# atx4vc.net
KiCad netlist of a schematic drawn in EAGLE
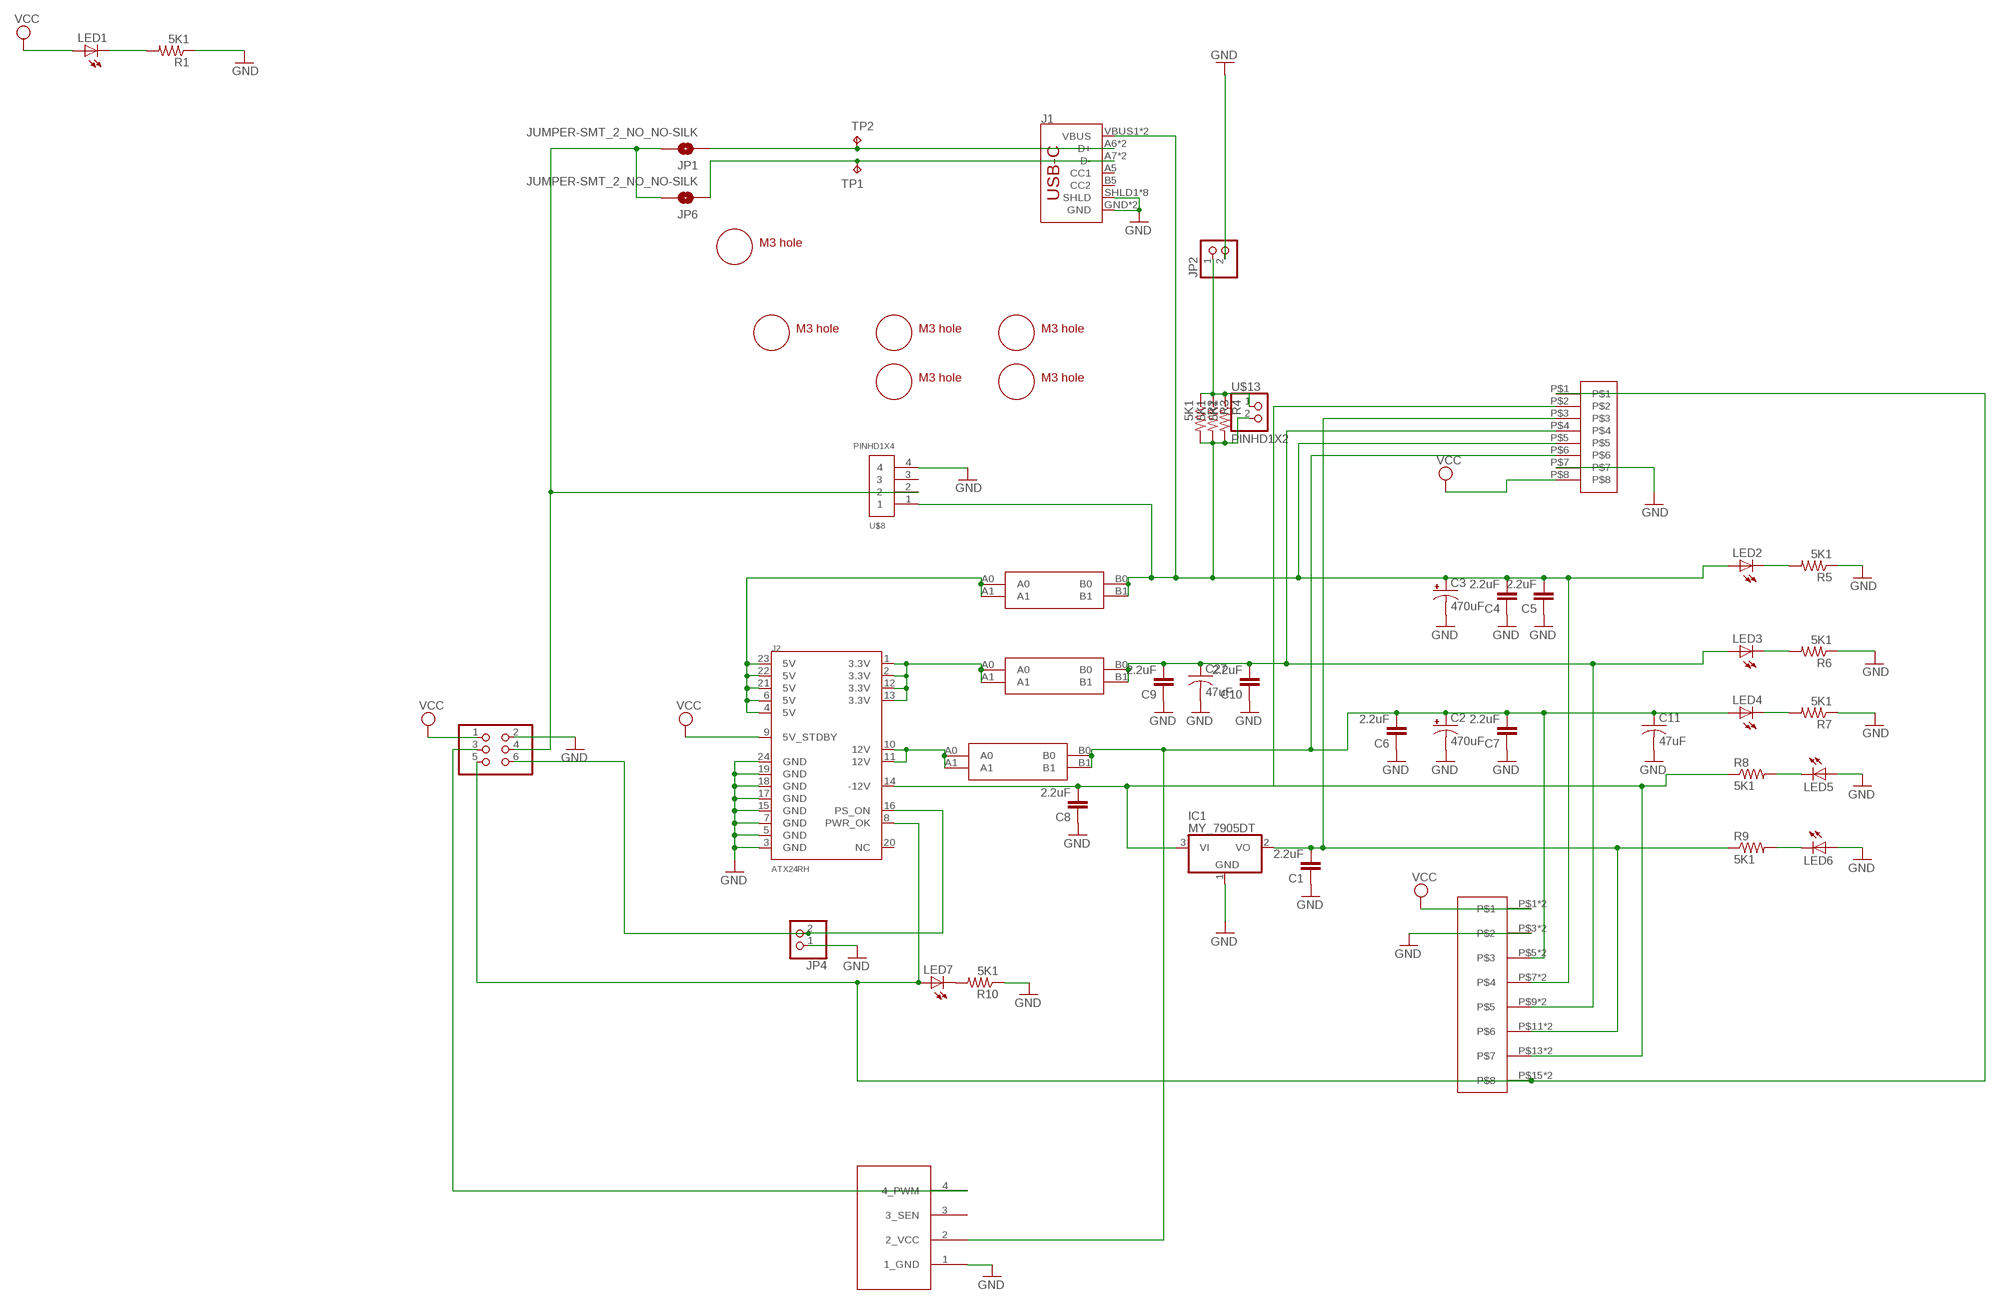
[diagram p0: schematic, sheet 1]

(export (version "E")
  (design (tool "Eeschema 10.0.6"))
  (components
    (comp (ref "C1")
      (value "2.2uF")
      (footprint "eagle-import:0805$1")
      (libsource (lib "eagle-import") (part "CAP0805"))
    )
    (comp (ref "C2")
      (value "470uF")
      (footprint "eagle-import:SMC_D")
      (libsource (lib "eagle-import") (part "CPOL-USSMCD"))
    )
    (comp (ref "C3")
      (value "470uF")
      (footprint "eagle-import:SMC_D")
      (libsource (lib "eagle-import") (part "CPOL-USSMCD"))
    )
    (comp (ref "C4")
      (value "2.2uF")
      (footprint "eagle-import:0805$1")
      (libsource (lib "eagle-import") (part "CAP0805"))
    )
    (comp (ref "C5")
      (value "2.2uF")
      (footprint "eagle-import:0805$1")
      (libsource (lib "eagle-import") (part "CAP0805"))
    )
    (comp (ref "C6")
      (value "2.2uF")
      (footprint "eagle-import:0805$1")
      (libsource (lib "eagle-import") (part "CAP0805"))
    )
    (comp (ref "C7")
      (value "2.2uF")
      (footprint "eagle-import:0805$1")
      (libsource (lib "eagle-import") (part "CAP0805"))
    )
    (comp (ref "C8")
      (value "2.2uF")
      (footprint "eagle-import:0805$1")
      (libsource (lib "eagle-import") (part "CAP0805"))
    )
    (comp (ref "C9")
      (value "2.2uF")
      (footprint "eagle-import:0805$1")
      (libsource (lib "eagle-import") (part "CAP0805"))
    )
    (comp (ref "C10")
      (value "2.2uF")
      (footprint "eagle-import:0805$1")
      (libsource (lib "eagle-import") (part "CAP0805"))
    )
    (comp (ref "C11")
      (value "47uF")
      (footprint "eagle-import:C1210")
      (libsource (lib "eagle-import") (part "C-USC1210"))
    )
    (comp (ref "C27")
      (value "47uF")
      (footprint "eagle-import:C1210")
      (libsource (lib "eagle-import") (part "C-USC1210"))
    )
    (comp (ref "IC1")
      (value "MY_7905DT")
      (footprint "eagle-import:ADAFRUIT_TO252")
      (libsource (lib "eagle-import") (part "MY_7905DT"))
    )
    (comp (ref "J1")
      (value "USB_C16PIN")
      (footprint "eagle-import:USB-C-16P")
      (libsource (lib "eagle-import") (part "USB_C16PIN"))
    )
    (comp (ref "J2")
      (value "ATX24RH")
      (footprint "eagle-import:ATX24_RIGHT_ANGLE")
      (libsource (lib "eagle-import") (part "ATX24RH"))
    )
    (comp (ref "JP1")
      (value "JUMPER-SMT_2_NO_NO-SILK")
      (footprint "eagle-import:SMT-JUMPER_2_NO_NO-SILK")
      (libsource (lib "eagle-import") (part "JUMPER-SMT_2_NO_NO-SILK"))
    )
    (comp (ref "JP2")
      (value "PINHD-1X2")
      (footprint "eagle-import:1X02")
      (libsource (lib "eagle-import") (part "PINHD-1X2"))
    )
    (comp (ref "JP3")
      (value "PINHD-2X3")
      (footprint "eagle-import:2X03")
      (libsource (lib "eagle-import") (part "PINHD-2X3"))
    )
    (comp (ref "JP4")
      (value "PINHD-1X2")
      (footprint "eagle-import:1X02")
      (libsource (lib "eagle-import") (part "PINHD-1X2"))
    )
    (comp (ref "JP5")
      (value "4PIN_FAN")
      (footprint "eagle-import:1X04")
      (libsource (lib "eagle-import") (part "4PIN_FAN"))
    )
    (comp (ref "JP6")
      (value "JUMPER-SMT_2_NO_NO-SILK")
      (footprint "eagle-import:SMT-JUMPER_2_NO_NO-SILK")
      (libsource (lib "eagle-import") (part "JUMPER-SMT_2_NO_NO-SILK"))
    )
    (comp (ref "LED1")
      (value "LEDCHIP-LED0805")
      (footprint "eagle-import:CHIP-LED0805")
      (libsource (lib "eagle-import") (part "LEDCHIP-LED0805"))
    )
    (comp (ref "LED2")
      (value "LEDCHIP-LED0805")
      (footprint "eagle-import:CHIP-LED0805")
      (libsource (lib "eagle-import") (part "LEDCHIP-LED0805"))
    )
    (comp (ref "LED3")
      (value "LEDCHIP-LED0805")
      (footprint "eagle-import:CHIP-LED0805")
      (libsource (lib "eagle-import") (part "LEDCHIP-LED0805"))
    )
    (comp (ref "LED4")
      (value "LEDCHIP-LED0805")
      (footprint "eagle-import:CHIP-LED0805")
      (libsource (lib "eagle-import") (part "LEDCHIP-LED0805"))
    )
    (comp (ref "LED5")
      (value "LEDCHIP-LED0805")
      (footprint "eagle-import:CHIP-LED0805")
      (libsource (lib "eagle-import") (part "LEDCHIP-LED0805"))
    )
    (comp (ref "LED6")
      (value "LEDCHIP-LED0805")
      (footprint "eagle-import:CHIP-LED0805")
      (libsource (lib "eagle-import") (part "LEDCHIP-LED0805"))
    )
    (comp (ref "LED7")
      (value "LEDCHIP-LED0805")
      (footprint "eagle-import:CHIP-LED0805")
      (libsource (lib "eagle-import") (part "LEDCHIP-LED0805"))
    )
    (comp (ref "R1")
      (value "5K1")
      (footprint "eagle-import:0805")
      (libsource (lib "eagle-import") (part "atx_power_control_RESISTOR0805-RES"))
    )
    (comp (ref "R2")
      (value "5K1")
      (footprint "eagle-import:0805")
      (libsource (lib "eagle-import") (part "atx_power_control_RESISTOR0805-RES"))
    )
    (comp (ref "R3")
      (value "5K1")
      (footprint "eagle-import:0805")
      (libsource (lib "eagle-import") (part "atx_power_control_RESISTOR0805-RES"))
    )
    (comp (ref "R4")
      (value "5K1")
      (footprint "eagle-import:0805")
      (libsource (lib "eagle-import") (part "atx_power_control_RESISTOR0805-RES"))
    )
    (comp (ref "R5")
      (value "5K1")
      (footprint "eagle-import:0805")
      (libsource (lib "eagle-import") (part "atx_power_control_RESISTOR0805-RES"))
    )
    (comp (ref "R6")
      (value "5K1")
      (footprint "eagle-import:0805")
      (libsource (lib "eagle-import") (part "atx_power_control_RESISTOR0805-RES"))
    )
    (comp (ref "R7")
      (value "5K1")
      (footprint "eagle-import:0805")
      (libsource (lib "eagle-import") (part "atx_power_control_RESISTOR0805-RES"))
    )
    (comp (ref "R8")
      (value "5K1")
      (footprint "eagle-import:0805")
      (libsource (lib "eagle-import") (part "RESISTOR0805-RES"))
    )
    (comp (ref "R9")
      (value "5K1")
      (footprint "eagle-import:0805")
      (libsource (lib "eagle-import") (part "RESISTOR0805-RES"))
    )
    (comp (ref "R10")
      (value "5K1")
      (footprint "eagle-import:0805")
      (libsource (lib "eagle-import") (part "atx_power_control_RESISTOR0805-RES"))
    )
    (comp (ref "TP1")
      (value "TPTP12R")
      (footprint "eagle-import:TP12R")
      (libsource (lib "eagle-import") (part "TPTP12R"))
    )
    (comp (ref "TP2")
      (value "TPTP12R")
      (footprint "eagle-import:TP12R")
      (libsource (lib "eagle-import") (part "TPTP12R"))
    )
    (comp (ref "U$1")
      (value "M3_MOUNTING_HOLE")
      (footprint "eagle-import:M3_MOUNTING_HOLE_PACK")
      (libsource (lib "eagle-import") (part "M3_MOUNTING_HOLE"))
    )
    (comp (ref "U$2")
      (value "M3_MOUNTING_HOLE")
      (footprint "eagle-import:M3_MOUNTING_HOLE_PACK")
      (libsource (lib "eagle-import") (part "M3_MOUNTING_HOLE"))
    )
    (comp (ref "U$3")
      (value "M3_MOUNTING_HOLE")
      (footprint "eagle-import:M3_MOUNTING_HOLE_PACK")
      (libsource (lib "eagle-import") (part "M3_MOUNTING_HOLE"))
    )
    (comp (ref "U$4")
      (value "M3_MOUNTING_HOLE")
      (footprint "eagle-import:M3_MOUNTING_HOLE_PACK")
      (libsource (lib "eagle-import") (part "M3_MOUNTING_HOLE"))
    )
    (comp (ref "U$5")
      (value "M3_MOUNTING_HOLE")
      (footprint "eagle-import:M3_MOUNTING_HOLE_PACK")
      (libsource (lib "eagle-import") (part "M3_MOUNTING_HOLE"))
    )
    (comp (ref "U$6")
      (value "M3_MOUNTING_HOLE")
      (footprint "eagle-import:M3_MOUNTING_HOLE_PACK")
      (libsource (lib "eagle-import") (part "M3_MOUNTING_HOLE"))
    )
    (comp (ref "U$7")
      (value "396_CONN_VH396_8P")
      (footprint "eagle-import:396_CONN_396_8P")
      (libsource (lib "eagle-import") (part "396_CONN_VH396_8P"))
    )
    (comp (ref "U$8")
      (value "PINHD1X4")
      (footprint "eagle-import:1X04-CLEANBIG")
      (libsource (lib "eagle-import") (part "PINHD1X4"))
    )
    (comp (ref "U$9")
      (value "CAR_FUSE_HOLDER3IN1")
      (footprint "eagle-import:FUSE_HOLDER_3IN1")
      (libsource (lib "eagle-import") (part "CAR_FUSE_HOLDER3IN1"))
    )
    (comp (ref "U$10")
      (value "CAR_FUSE_HOLDER3IN1")
      (footprint "eagle-import:FUSE_HOLDER_3IN1")
      (libsource (lib "eagle-import") (part "CAR_FUSE_HOLDER3IN1"))
    )
    (comp (ref "U$11")
      (value "CAR_FUSE_HOLDER3IN1")
      (footprint "eagle-import:FUSE_HOLDER_3IN1")
      (libsource (lib "eagle-import") (part "CAR_FUSE_HOLDER3IN1"))
    )
    (comp (ref "U$12")
      (value "DG2204R-5.0-8DG2204-8")
      (footprint "eagle-import:DG2204R-8")
      (libsource (lib "eagle-import") (part "DG2204R-5.0-8DG2204-8"))
    )
    (comp (ref "U$13")
      (value "PINHD1X2")
      (footprint "eagle-import:1X02")
      (libsource (lib "eagle-import") (part "PINHD1X2"))
    )
  )
  (nets
    (net (code "1") (name "GND") (class "Default")
      (node (ref "C1") (pin "1") (pinfunction "1_1") (pintype "passive"))
      (node (ref "C10") (pin "1") (pinfunction "1_1") (pintype "passive"))
      (node (ref "C11") (pin "2") (pinfunction "2_2") (pintype "passive"))
      (node (ref "C2") (pin "-") (pinfunction "-_-") (pintype "passive"))
      (node (ref "C27") (pin "2") (pinfunction "2_2") (pintype "passive"))
      (node (ref "C3") (pin "-") (pinfunction "-_-") (pintype "passive"))
      (node (ref "C4") (pin "1") (pinfunction "1_1") (pintype "passive"))
      (node (ref "C5") (pin "1") (pinfunction "1_1") (pintype "passive"))
      (node (ref "C6") (pin "1") (pinfunction "1_1") (pintype "passive"))
      (node (ref "C7") (pin "1") (pinfunction "1_1") (pintype "passive"))
      (node (ref "C8") (pin "1") (pinfunction "1_1") (pintype "passive"))
      (node (ref "C9") (pin "1") (pinfunction "1_1") (pintype "passive"))
      (node (ref "IC1") (pin "1") (pinfunction "GND_1") (pintype "passive"))
      (node (ref "J1") (pin "GND") (pinfunction "GND_GND") (pintype "bidirectional"))
      (node (ref "J1") (pin "GND2") (pinfunction "GND_GND2") (pintype "bidirectional"))
      (node (ref "J1") (pin "SHLD1") (pinfunction "SHLD_SHLD1") (pintype "bidirectional"))
      (node (ref "J1") (pin "SHLD2") (pinfunction "SHLD_SHLD2") (pintype "bidirectional"))
      (node (ref "J1") (pin "SHLD3") (pinfunction "SHLD_SHLD3") (pintype "bidirectional"))
      (node (ref "J1") (pin "SHLD4") (pinfunction "SHLD_SHLD4") (pintype "bidirectional"))
      (node (ref "J1") (pin "SHLD5") (pinfunction "SHLD_SHLD5") (pintype "bidirectional"))
      (node (ref "J1") (pin "SHLD6") (pinfunction "SHLD_SHLD6") (pintype "bidirectional"))
      (node (ref "J1") (pin "SHLD7") (pinfunction "SHLD_SHLD7") (pintype "bidirectional"))
      (node (ref "J1") (pin "SHLD8") (pinfunction "SHLD_SHLD8") (pintype "bidirectional"))
      (node (ref "J2") (pin "15") (pinfunction "GND_15") (pintype "bidirectional"))
      (node (ref "J2") (pin "17") (pinfunction "GND_17") (pintype "bidirectional"))
      (node (ref "J2") (pin "18") (pinfunction "GND_18") (pintype "bidirectional"))
      (node (ref "J2") (pin "19") (pinfunction "GND_19") (pintype "bidirectional"))
      (node (ref "J2") (pin "24") (pinfunction "GND_24") (pintype "bidirectional"))
      (node (ref "J2") (pin "3") (pinfunction "GND_3") (pintype "bidirectional"))
      (node (ref "J2") (pin "5") (pinfunction "GND_5") (pintype "bidirectional"))
      (node (ref "J2") (pin "7") (pinfunction "GND_7") (pintype "bidirectional"))
      (node (ref "JP2") (pin "2") (pinfunction "2_2") (pintype "passive"))
      (node (ref "JP3") (pin "2") (pinfunction "2_2") (pintype "passive"))
      (node (ref "JP4") (pin "1") (pinfunction "1_1") (pintype "passive"))
      (node (ref "JP5") (pin "1") (pinfunction "1_GND_1") (pintype "passive"))
      (node (ref "LED5") (pin "A") (pinfunction "A_A") (pintype "passive"))
      (node (ref "LED6") (pin "A") (pinfunction "A_A") (pintype "passive"))
      (node (ref "R1") (pin "1") (pinfunction "1_1") (pintype "passive"))
      (node (ref "R10") (pin "1") (pinfunction "1_1") (pintype "passive"))
      (node (ref "R5") (pin "1") (pinfunction "1_1") (pintype "passive"))
      (node (ref "R6") (pin "1") (pinfunction "1_1") (pintype "passive"))
      (node (ref "R7") (pin "1") (pinfunction "1_1") (pintype "passive"))
      (node (ref "U$12") (pin "P$3") (pinfunction "P$2_P$3") (pintype "bidirectional"))
      (node (ref "U$12") (pin "P$4") (pinfunction "P$2_P$4") (pintype "bidirectional"))
      (node (ref "U$7") (pin "P$7") (pinfunction "P$7_P$7") (pintype "bidirectional"))
      (node (ref "U$8") (pin "4") (pinfunction "4_4") (pintype "bidirectional"))
    )
    (net (code "2") (name "Net-(C3-Pad+)") (class "Default")
      (node (ref "C3") (pin "+") (pinfunction "+_+") (pintype "passive"))
      (node (ref "C4") (pin "2") (pinfunction "2_2") (pintype "passive"))
      (node (ref "C5") (pin "2") (pinfunction "2_2") (pintype "passive"))
      (node (ref "J1") (pin "VBUS1") (pinfunction "VBUS_VBUS1") (pintype "bidirectional"))
      (node (ref "J1") (pin "VBUS2") (pinfunction "VBUS_VBUS2") (pintype "bidirectional"))
      (node (ref "LED2") (pin "A") (pinfunction "A_A") (pintype "passive"))
      (node (ref "R2") (pin "2") (pinfunction "2_2") (pintype "passive"))
      (node (ref "R3") (pin "2") (pinfunction "2_2") (pintype "passive"))
      (node (ref "R4") (pin "2") (pinfunction "2_2") (pintype "passive"))
      (node (ref "U$12") (pin "P$7") (pinfunction "P$4_P$7") (pintype "bidirectional"))
      (node (ref "U$12") (pin "P$8") (pinfunction "P$4_P$8") (pintype "bidirectional"))
      (node (ref "U$13") (pin "2") (pinfunction "2_2") (pintype "passive"))
      (node (ref "U$7") (pin "P$5") (pinfunction "P$5_P$5") (pintype "bidirectional"))
      (node (ref "U$8") (pin "1") (pinfunction "1_1") (pintype "bidirectional"))
      (node (ref "U$9") (pin "B0") (pinfunction "B0_B0") (pintype "bidirectional"))
      (node (ref "U$9") (pin "B1") (pinfunction "B1_B1") (pintype "bidirectional"))
    )
    (net (code "3") (name "Net-(C10-Pad2)") (class "Default")
      (node (ref "C10") (pin "2") (pinfunction "2_2") (pintype "passive"))
      (node (ref "C27") (pin "1") (pinfunction "1_1") (pintype "passive"))
      (node (ref "C9") (pin "2") (pinfunction "2_2") (pintype "passive"))
      (node (ref "LED3") (pin "A") (pinfunction "A_A") (pintype "passive"))
      (node (ref "U$10") (pin "B0") (pinfunction "B0_B0") (pintype "bidirectional"))
      (node (ref "U$10") (pin "B1") (pinfunction "B1_B1") (pintype "bidirectional"))
      (node (ref "U$12") (pin "P$10") (pinfunction "P$5_P$10") (pintype "bidirectional"))
      (node (ref "U$12") (pin "P$9") (pinfunction "P$5_P$9") (pintype "bidirectional"))
      (node (ref "U$7") (pin "P$4") (pinfunction "P$4_P$4") (pintype "bidirectional"))
    )
    (net (code "4") (name "Net-(IC1-VI)") (class "Default")
      (node (ref "C8") (pin "2") (pinfunction "2_2") (pintype "passive"))
      (node (ref "IC1") (pin "3") (pinfunction "VI_3") (pintype "input"))
      (node (ref "J2") (pin "14") (pinfunction "-12V_14") (pintype "bidirectional"))
      (node (ref "R8") (pin "1") (pinfunction "1_1") (pintype "passive"))
      (node (ref "U$12") (pin "P$13") (pinfunction "P$7_P$13") (pintype "bidirectional"))
      (node (ref "U$12") (pin "P$14") (pinfunction "P$7_P$14") (pintype "bidirectional"))
      (node (ref "U$7") (pin "P$2") (pinfunction "P$2_P$2") (pintype "bidirectional"))
    )
    (net (code "5") (name "Net-(IC1-VO)") (class "Default")
      (node (ref "C1") (pin "2") (pinfunction "2_2") (pintype "passive"))
      (node (ref "IC1") (pin "2") (pinfunction "VO_2") (pintype "passive"))
      (node (ref "R9") (pin "1") (pinfunction "1_1") (pintype "passive"))
      (node (ref "U$12") (pin "P$11") (pinfunction "P$6_P$11") (pintype "bidirectional"))
      (node (ref "U$12") (pin "P$12") (pinfunction "P$6_P$12") (pintype "bidirectional"))
      (node (ref "U$7") (pin "P$3") (pinfunction "P$3_P$3") (pintype "bidirectional"))
    )
    (net (code "6") (name "Net-(J1-D+-PadA6)") (class "Default")
      (node (ref "J1") (pin "A6") (pinfunction "D+_A6") (pintype "bidirectional"))
      (node (ref "J1") (pin "B6") (pinfunction "D+_B6") (pintype "bidirectional"))
      (node (ref "JP1") (pin "1") (pinfunction "1_1") (pintype "passive"))
      (node (ref "TP2") (pin "TP") (pinfunction "TP_TP") (pintype "input"))
    )
    (net (code "7") (name "Net-(J1-D--PadA7)") (class "Default")
      (node (ref "J1") (pin "A7") (pinfunction "D-_A7") (pintype "bidirectional"))
      (node (ref "J1") (pin "B7") (pinfunction "D-_B7") (pintype "bidirectional"))
      (node (ref "JP6") (pin "1") (pinfunction "1_1") (pintype "passive"))
      (node (ref "TP1") (pin "TP") (pinfunction "TP_TP") (pintype "input"))
    )
    (net (code "8") (name "Net-(J2-3.3V-Pad1)") (class "Default")
      (node (ref "J2") (pin "1") (pinfunction "3.3V_1") (pintype "bidirectional"))
      (node (ref "J2") (pin "12") (pinfunction "3.3V_12") (pintype "bidirectional"))
      (node (ref "J2") (pin "13") (pinfunction "3.3V_13") (pintype "bidirectional"))
      (node (ref "J2") (pin "2") (pinfunction "3.3V_2") (pintype "bidirectional"))
      (node (ref "U$10") (pin "A0") (pinfunction "A0_A0") (pintype "bidirectional"))
      (node (ref "U$10") (pin "A1") (pinfunction "A1_A1") (pintype "bidirectional"))
    )
    (net (code "9") (name "Net-(J2-5V-Pad21)") (class "Default")
      (node (ref "J2") (pin "21") (pinfunction "5V_21") (pintype "bidirectional"))
      (node (ref "J2") (pin "22") (pinfunction "5V_22") (pintype "bidirectional"))
      (node (ref "J2") (pin "23") (pinfunction "5V_23") (pintype "bidirectional"))
      (node (ref "J2") (pin "4") (pinfunction "5V_4") (pintype "bidirectional"))
      (node (ref "J2") (pin "6") (pinfunction "5V_6") (pintype "bidirectional"))
      (node (ref "U$9") (pin "A0") (pinfunction "A0_A0") (pintype "bidirectional"))
      (node (ref "U$9") (pin "A1") (pinfunction "A1_A1") (pintype "bidirectional"))
    )
    (net (code "10") (name "Net-(J2-12V-Pad10)") (class "Default")
      (node (ref "J2") (pin "10") (pinfunction "12V_10") (pintype "bidirectional"))
      (node (ref "J2") (pin "11") (pinfunction "12V_11") (pintype "bidirectional"))
      (node (ref "U$11") (pin "A0") (pinfunction "A0_A0") (pintype "bidirectional"))
      (node (ref "U$11") (pin "A1") (pinfunction "A1_A1") (pintype "bidirectional"))
    )
    (net (code "11") (name "Net-(J2-PS_ON)") (class "Default")
      (node (ref "J2") (pin "16") (pinfunction "PS_ON_16") (pintype "bidirectional"))
      (node (ref "JP3") (pin "6") (pinfunction "6_6") (pintype "passive"))
      (node (ref "JP4") (pin "2") (pinfunction "2_2") (pintype "passive"))
    )
    (net (code "12") (name "Net-(J2-PWR_OK)") (class "Default")
      (node (ref "J2") (pin "8") (pinfunction "PWR_OK_8") (pintype "bidirectional"))
      (node (ref "JP3") (pin "5") (pinfunction "5_5") (pintype "passive"))
      (node (ref "LED7") (pin "A") (pinfunction "A_A") (pintype "passive"))
      (node (ref "U$12") (pin "P$15") (pinfunction "P$8_P$15") (pintype "bidirectional"))
      (node (ref "U$12") (pin "P$16") (pinfunction "P$8_P$16") (pintype "bidirectional"))
      (node (ref "U$7") (pin "P$1") (pinfunction "P$1_P$1") (pintype "bidirectional"))
    )
    (net (code "13") (name "Net-(JP1-Pad2)") (class "Default")
      (node (ref "JP1") (pin "2") (pinfunction "2_2") (pintype "passive"))
      (node (ref "JP3") (pin "4") (pinfunction "4_4") (pintype "passive"))
      (node (ref "JP6") (pin "2") (pinfunction "2_2") (pintype "passive"))
      (node (ref "U$8") (pin "2") (pinfunction "2_2") (pintype "bidirectional"))
    )
    (net (code "14") (name "Net-(JP2-Pad1)") (class "Default")
      (node (ref "JP2") (pin "1") (pinfunction "1_1") (pintype "passive"))
      (node (ref "R2") (pin "1") (pinfunction "1_1") (pintype "passive"))
      (node (ref "R3") (pin "1") (pinfunction "1_1") (pintype "passive"))
      (node (ref "R4") (pin "1") (pinfunction "1_1") (pintype "passive"))
      (node (ref "U$13") (pin "1") (pinfunction "1_1") (pintype "passive"))
    )
    (net (code "15") (name "Net-(JP5-2_VCC)") (class "Default")
      (node (ref "C11") (pin "1") (pinfunction "1_1") (pintype "passive"))
      (node (ref "C2") (pin "+") (pinfunction "+_+") (pintype "passive"))
      (node (ref "C6") (pin "2") (pinfunction "2_2") (pintype "passive"))
      (node (ref "C7") (pin "2") (pinfunction "2_2") (pintype "passive"))
      (node (ref "JP5") (pin "2") (pinfunction "2_VCC_2") (pintype "passive"))
      (node (ref "LED4") (pin "A") (pinfunction "A_A") (pintype "passive"))
      (node (ref "U$11") (pin "B0") (pinfunction "B0_B0") (pintype "bidirectional"))
      (node (ref "U$11") (pin "B1") (pinfunction "B1_B1") (pintype "bidirectional"))
      (node (ref "U$12") (pin "P$5") (pinfunction "P$3_P$5") (pintype "bidirectional"))
      (node (ref "U$12") (pin "P$6") (pinfunction "P$3_P$6") (pintype "bidirectional"))
      (node (ref "U$7") (pin "P$6") (pinfunction "P$6_P$6") (pintype "bidirectional"))
    )
    (net (code "16") (name "Net-(JP5-4_PWM)") (class "Default")
      (node (ref "JP3") (pin "3") (pinfunction "3_3") (pintype "passive"))
      (node (ref "JP5") (pin "4") (pinfunction "4_PWM_4") (pintype "passive"))
    )
    (net (code "17") (name "Net-(LED1-PadC)") (class "Default")
      (node (ref "LED1") (pin "C") (pinfunction "C_C") (pintype "passive"))
      (node (ref "R1") (pin "2") (pinfunction "2_2") (pintype "passive"))
    )
    (net (code "18") (name "Net-(LED2-PadC)") (class "Default")
      (node (ref "LED2") (pin "C") (pinfunction "C_C") (pintype "passive"))
      (node (ref "R5") (pin "2") (pinfunction "2_2") (pintype "passive"))
    )
    (net (code "19") (name "Net-(LED3-PadC)") (class "Default")
      (node (ref "LED3") (pin "C") (pinfunction "C_C") (pintype "passive"))
      (node (ref "R6") (pin "2") (pinfunction "2_2") (pintype "passive"))
    )
    (net (code "20") (name "Net-(LED4-PadC)") (class "Default")
      (node (ref "LED4") (pin "C") (pinfunction "C_C") (pintype "passive"))
      (node (ref "R7") (pin "2") (pinfunction "2_2") (pintype "passive"))
    )
    (net (code "21") (name "Net-(LED5-PadC)") (class "Default")
      (node (ref "LED5") (pin "C") (pinfunction "C_C") (pintype "passive"))
      (node (ref "R8") (pin "2") (pinfunction "2_2") (pintype "passive"))
    )
    (net (code "22") (name "Net-(LED6-PadC)") (class "Default")
      (node (ref "LED6") (pin "C") (pinfunction "C_C") (pintype "passive"))
      (node (ref "R9") (pin "2") (pinfunction "2_2") (pintype "passive"))
    )
    (net (code "23") (name "Net-(LED7-PadC)") (class "Default")
      (node (ref "LED7") (pin "C") (pinfunction "C_C") (pintype "passive"))
      (node (ref "R10") (pin "2") (pinfunction "2_2") (pintype "passive"))
    )
    (net (code "24") (name "VCC") (class "Default")
      (node (ref "J2") (pin "9") (pinfunction "5V_STDBY_9") (pintype "bidirectional"))
      (node (ref "JP3") (pin "1") (pinfunction "1_1") (pintype "passive"))
      (node (ref "LED1") (pin "A") (pinfunction "A_A") (pintype "passive"))
      (node (ref "U$12") (pin "P$1") (pinfunction "P$1_P$1") (pintype "bidirectional"))
      (node (ref "U$12") (pin "P$2") (pinfunction "P$1_P$2") (pintype "bidirectional"))
      (node (ref "U$7") (pin "P$8") (pinfunction "P$8_P$8") (pintype "bidirectional"))
    )
    (net (code "25") (name "unconnected-(J1-CC1-PadA5)") (class "Default")
      (node (ref "J1") (pin "A5") (pinfunction "CC1_A5") (pintype "bidirectional"))
    )
    (net (code "26") (name "unconnected-(J1-CC2-PadB5)") (class "Default")
      (node (ref "J1") (pin "B5") (pinfunction "CC2_B5") (pintype "bidirectional"))
    )
    (net (code "27") (name "unconnected-(J2-NC-Pad20)") (class "Default")
      (node (ref "J2") (pin "20") (pinfunction "NC_20") (pintype "bidirectional"))
    )
    (net (code "28") (name "unconnected-(JP5-3_SEN-Pad3)") (class "Default")
      (node (ref "JP5") (pin "3") (pinfunction "3_SEN_3") (pintype "passive"))
    )
    (net (code "29") (name "unconnected-(U$8-Pad3)") (class "Default")
      (node (ref "U$8") (pin "3") (pinfunction "3_3") (pintype "bidirectional"))
    )
  )
)
